# sd_card_spi_FRAM.net
KiCad netlist of a schematic drawn in EAGLE
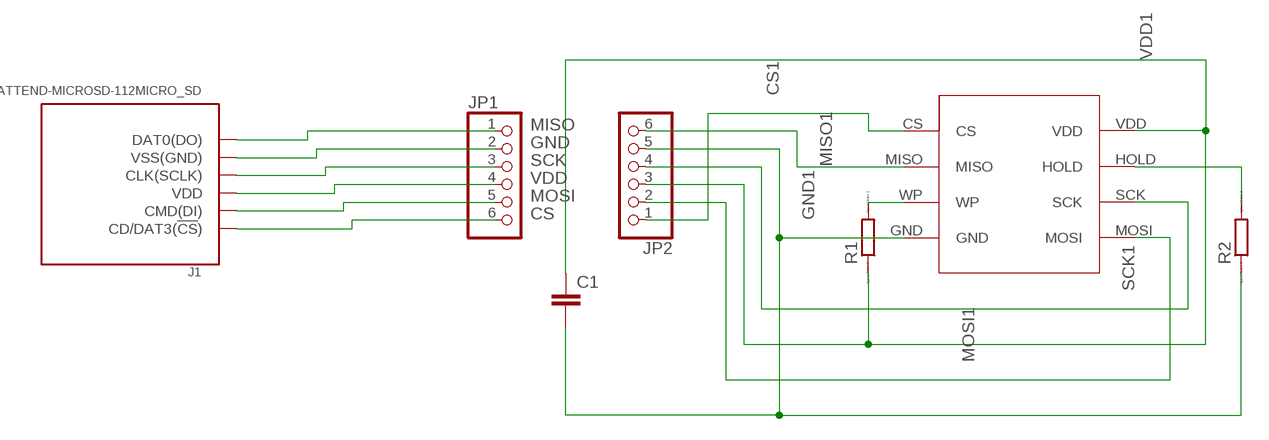
[diagram p0: schematic, sheet 1]

(export (version "E")
  (design (tool "Eeschema 10.0.6"))
  (components
    (comp (ref "C1")
      (value "C5/5")
      (footprint "eagle-import:C5B5")
      (libsource (lib "eagle-import") (part "C5/5"))
    )
    (comp (ref "J1")
      (value "ATTEND-MICROSD-112MICRO_SD")
      (footprint "eagle-import:MICROSD_MICROSD_CARD")
      (libsource (lib "eagle-import") (part "ATTEND-MICROSD-112MICRO_SD"))
    )
    (comp (ref "JP1")
      (value "PINHD-1X6")
      (footprint "eagle-import:1X06")
      (libsource (lib "eagle-import") (part "PINHD-1X6"))
    )
    (comp (ref "JP2")
      (value "PINHD-1X6")
      (footprint "eagle-import:1X06")
      (libsource (lib "eagle-import") (part "PINHD-1X6"))
    )
    (comp (ref "R1")
      (value "R-EU_0207_10")
      (footprint "eagle-import:0207_10")
      (libsource (lib "eagle-import") (part "R-EU_0207_10"))
    )
    (comp (ref "R2")
      (value "R-EU_0207_10")
      (footprint "eagle-import:0207_10")
      (libsource (lib "eagle-import") (part "R-EU_0207_10"))
    )
    (comp (ref "U$1")
      (value "MB85RS")
      (footprint "eagle-import:SOIC8")
      (libsource (lib "eagle-import") (part "MB85RS"))
    )
  )
  (nets
    (net (code "1") (name "/CS") (class "Default")
      (node (ref "J1") (pin "2") (pinfunction "CD/DAT3(~{CS})_2") (pintype "bidirectional"))
      (node (ref "JP1") (pin "6") (pinfunction "6_6") (pintype "passive"))
    )
    (net (code "2") (name "/CS1") (class "Default")
      (node (ref "JP2") (pin "1") (pinfunction "1_1") (pintype "passive"))
      (node (ref "U$1") (pin "CS") (pinfunction "CS_CS") (pintype "bidirectional"))
    )
    (net (code "3") (name "/GND") (class "Default")
      (node (ref "J1") (pin "6") (pinfunction "VSS(GND)_6") (pintype "power_in"))
      (node (ref "JP1") (pin "2") (pinfunction "2_2") (pintype "passive"))
    )
    (net (code "4") (name "/GND1") (class "Default")
      (node (ref "C1") (pin "2") (pinfunction "2_2") (pintype "passive"))
      (node (ref "JP2") (pin "5") (pinfunction "5_5") (pintype "passive"))
      (node (ref "R2") (pin "1") (pinfunction "1_1") (pintype "passive"))
      (node (ref "U$1") (pin "GND") (pinfunction "GND_GND") (pintype "bidirectional"))
    )
    (net (code "5") (name "/MISO") (class "Default")
      (node (ref "J1") (pin "7") (pinfunction "DAT0(DO)_7") (pintype "bidirectional"))
      (node (ref "JP1") (pin "1") (pinfunction "1_1") (pintype "passive"))
    )
    (net (code "6") (name "/MISO1") (class "Default")
      (node (ref "JP2") (pin "6") (pinfunction "6_6") (pintype "passive"))
      (node (ref "U$1") (pin "MISO") (pinfunction "MISO_MISO") (pintype "bidirectional"))
    )
    (net (code "7") (name "/MOSI") (class "Default")
      (node (ref "J1") (pin "3") (pinfunction "CMD(DI)_3") (pintype "bidirectional"))
      (node (ref "JP1") (pin "5") (pinfunction "5_5") (pintype "passive"))
    )
    (net (code "8") (name "/MOSI1") (class "Default")
      (node (ref "JP2") (pin "2") (pinfunction "2_2") (pintype "passive"))
      (node (ref "U$1") (pin "MOSI") (pinfunction "MOSI_MOSI") (pintype "bidirectional"))
    )
    (net (code "9") (name "/SCK") (class "Default")
      (node (ref "J1") (pin "5") (pinfunction "CLK(SCLK)_5") (pintype "bidirectional"))
      (node (ref "JP1") (pin "3") (pinfunction "3_3") (pintype "passive"))
    )
    (net (code "10") (name "/SCK1") (class "Default")
      (node (ref "JP2") (pin "4") (pinfunction "4_4") (pintype "passive"))
      (node (ref "U$1") (pin "SCK") (pinfunction "SCK_SCK") (pintype "bidirectional"))
    )
    (net (code "11") (name "/VDD") (class "Default")
      (node (ref "J1") (pin "4") (pinfunction "VDD_4") (pintype "power_in"))
      (node (ref "JP1") (pin "4") (pinfunction "4_4") (pintype "passive"))
    )
    (net (code "12") (name "/VDD1") (class "Default")
      (node (ref "C1") (pin "1") (pinfunction "1_1") (pintype "passive"))
      (node (ref "JP2") (pin "3") (pinfunction "3_3") (pintype "passive"))
      (node (ref "R1") (pin "1") (pinfunction "1_1") (pintype "passive"))
      (node (ref "U$1") (pin "VDD") (pinfunction "VDD_VDD") (pintype "bidirectional"))
    )
    (net (code "13") (name "Net-(R1-Pad2)") (class "Default")
      (node (ref "R1") (pin "2") (pinfunction "2_2") (pintype "passive"))
      (node (ref "U$1") (pin "WP") (pinfunction "WP_WP") (pintype "bidirectional"))
    )
    (net (code "14") (name "Net-(R2-Pad2)") (class "Default")
      (node (ref "R2") (pin "2") (pinfunction "2_2") (pintype "passive"))
      (node (ref "U$1") (pin "HOLD") (pinfunction "HOLD_HOLD") (pintype "bidirectional"))
    )
  )
)
